# Supply.net
KiCad netlist of a schematic drawn in Altium Designer
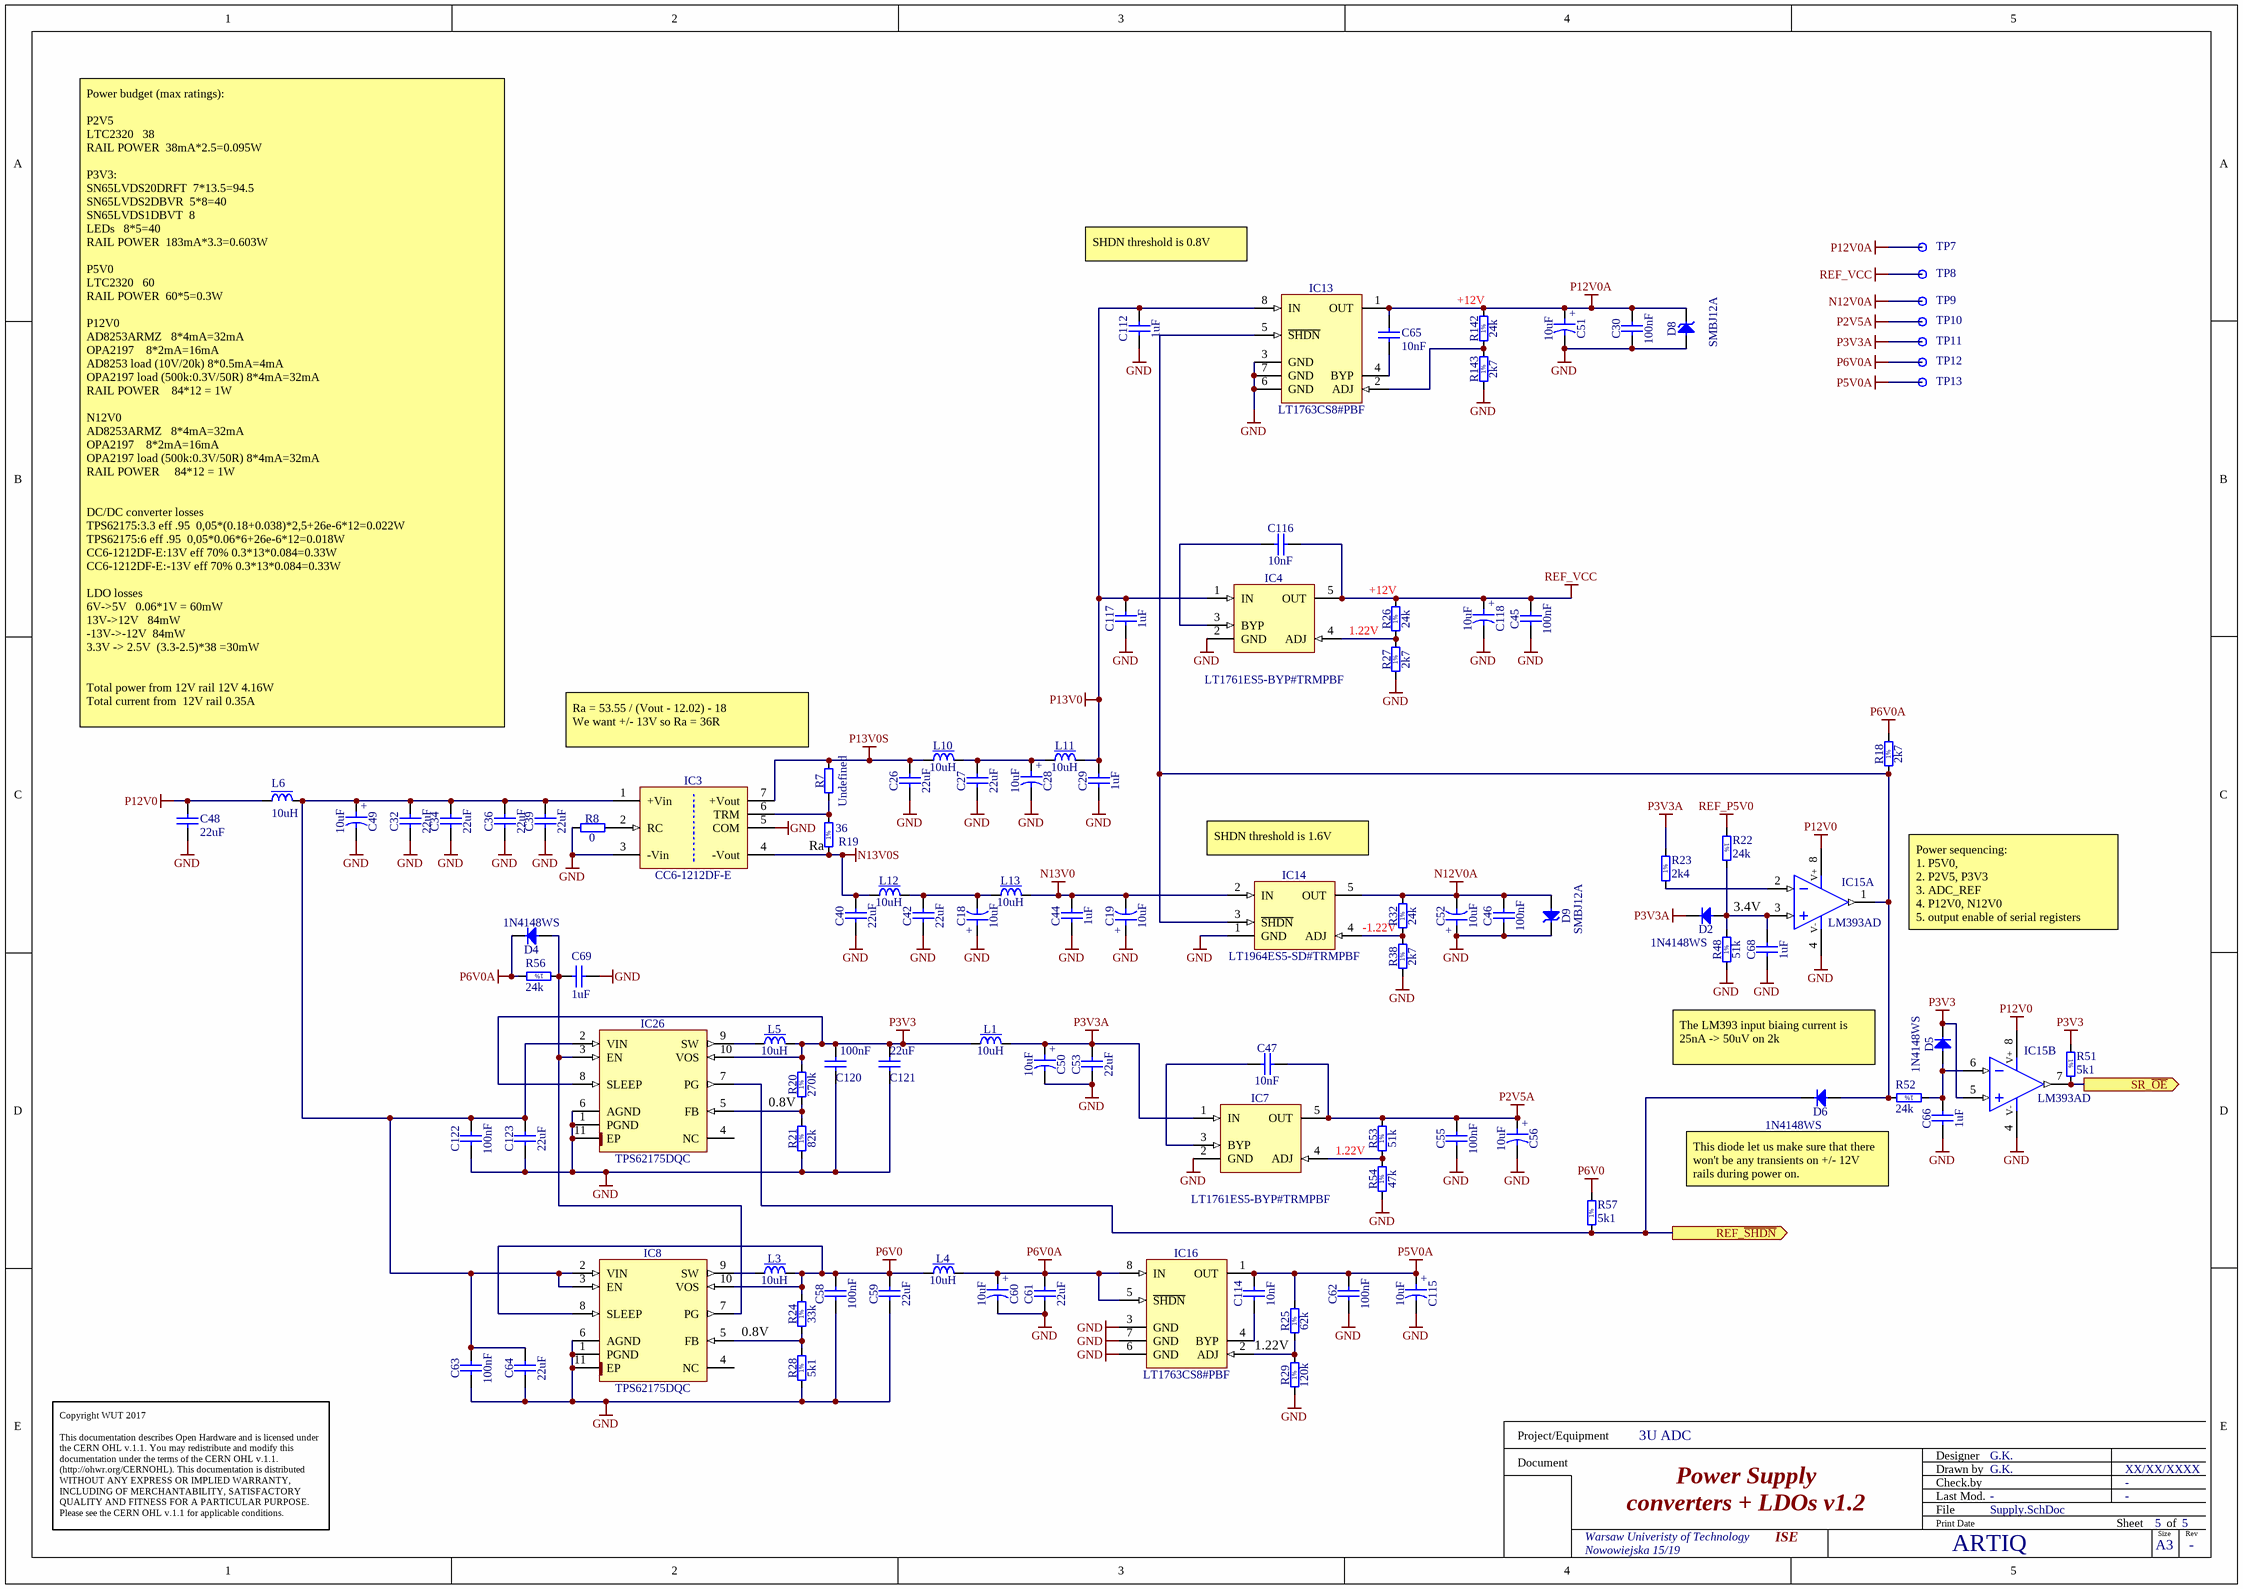
[diagram p0: Supply.SchDoc]

(export (version "E")
  (design (tool "Eeschema 10.0.6"))
  (components
    (comp (ref "C18")
      (value "10uF")
      (footprint "CAPMP3216X180N")
      (description "Polarised capacitor")
      (fields (field (name "PART NUMBER") "CTE3216-18_10UF_16V_20%_AVX_TCJ") (field (name "VOLTAGE") "16V"))
      (libsource (lib "Capacitors") (part "Capacitor - polarized"))
    )
    (comp (ref "C19")
      (value "10uF")
      (footprint "CAPMP3216X180N")
      (description "Polarised capacitor")
      (fields (field (name "PART NUMBER") "CTE3216-18_10UF_16V_20%_AVX_TCJ") (field (name "VOLTAGE") "16V"))
      (libsource (lib "Capacitors") (part "Capacitor - polarized"))
    )
    (comp (ref "C26")
      (value "22uF")
      (footprint "CAPC2012X135N")
      (description "Non-polarised capacitor")
      (fields (field (name "PART NUMBER") "CC0805_22UF_16V_10%_X5R") (field (name "VOLTAGE") "16V"))
      (libsource (lib "Capacitors") (part "Capacitor - non polarized"))
    )
    (comp (ref "C27")
      (value "22uF")
      (footprint "CAPC2012X135N")
      (description "Non-polarised capacitor")
      (fields (field (name "PART NUMBER") "CC0805_22UF_16V_10%_X5R") (field (name "VOLTAGE") "16V"))
      (libsource (lib "Capacitors") (part "Capacitor - non polarized"))
    )
    (comp (ref "C28")
      (value "10uF")
      (footprint "CAPMP3216X180N")
      (description "Polarised capacitor")
      (fields (field (name "PART NUMBER") "CTE3216-18_10UF_16V_20%_AVX_TCJ") (field (name "VOLTAGE") "16V"))
      (libsource (lib "Capacitors") (part "Capacitor - polarized"))
    )
    (comp (ref "C29")
      (value "1uF")
      (footprint "CAPC1608X87N")
      (description "Non-polarised capacitor")
      (fields (field (name "PART NUMBER") "CC0603_1UF_25V_10%_X7R") (field (name "VOLTAGE") "25V"))
      (libsource (lib "Capacitors") (part "Capacitor - non polarized"))
    )
    (comp (ref "C30")
      (value "100nF")
      (footprint "CAPC1005X55N")
      (description "Non-polarised capacitor")
      (fields (field (name "PART NUMBER") "CC0402_100NF_16V_10%_X5R") (field (name "VOLTAGE") "16V"))
      (libsource (lib "Capacitors") (part "Capacitor - non polarized"))
    )
    (comp (ref "C32")
      (value "22uF")
      (footprint "CAPC2012X135N")
      (description "Non-polarised capacitor")
      (fields (field (name "PART NUMBER") "CC0805_22UF_16V_10%_X5R") (field (name "VOLTAGE") "16V"))
      (libsource (lib "Capacitors") (part "Capacitor - non polarized"))
    )
    (comp (ref "C34")
      (value "22uF")
      (footprint "CAPC2012X135N")
      (description "Non-polarised capacitor")
      (fields (field (name "PART NUMBER") "CC0805_22UF_16V_10%_X5R") (field (name "VOLTAGE") "16V"))
      (libsource (lib "Capacitors") (part "Capacitor - non polarized"))
    )
    (comp (ref "C36")
      (value "22uF")
      (footprint "CAPC2012X135N")
      (description "Non-polarised capacitor")
      (fields (field (name "PART NUMBER") "CC0805_22UF_16V_10%_X5R") (field (name "VOLTAGE") "16V"))
      (libsource (lib "Capacitors") (part "Capacitor - non polarized"))
    )
    (comp (ref "C39")
      (value "22uF")
      (footprint "CAPC2012X135N")
      (description "Non-polarised capacitor")
      (fields (field (name "PART NUMBER") "CC0805_22UF_16V_10%_X5R") (field (name "VOLTAGE") "16V"))
      (libsource (lib "Capacitors") (part "Capacitor - non polarized"))
    )
    (comp (ref "C40")
      (value "22uF")
      (footprint "CAPC2012X135N")
      (description "Non-polarised capacitor")
      (fields (field (name "PART NUMBER") "CC0805_22UF_16V_10%_X5R") (field (name "VOLTAGE") "16V"))
      (libsource (lib "Capacitors") (part "Capacitor - non polarized"))
    )
    (comp (ref "C42")
      (value "22uF")
      (footprint "CAPC2012X135N")
      (description "Non-polarised capacitor")
      (fields (field (name "PART NUMBER") "CC0805_22UF_16V_10%_X5R") (field (name "VOLTAGE") "16V"))
      (libsource (lib "Capacitors") (part "Capacitor - non polarized"))
    )
    (comp (ref "C44")
      (value "1uF")
      (footprint "CAPC1608X87N")
      (description "Non-polarised capacitor")
      (fields (field (name "PART NUMBER") "CC0603_1UF_25V_10%_X7R") (field (name "VOLTAGE") "25V"))
      (libsource (lib "Capacitors") (part "Capacitor - non polarized"))
    )
    (comp (ref "C45")
      (value "100nF")
      (footprint "CAPC1005X55N")
      (description "Non-polarised capacitor")
      (fields (field (name "PART NUMBER") "CC0402_100NF_16V_10%_X5R") (field (name "VOLTAGE") "16V"))
      (libsource (lib "Capacitors") (part "Capacitor - non polarized"))
    )
    (comp (ref "C46")
      (value "100nF")
      (footprint "CAPC1005X55N")
      (description "Non-polarised capacitor")
      (fields (field (name "PART NUMBER") "CC0402_100NF_16V_10%_X5R") (field (name "VOLTAGE") "16V"))
      (libsource (lib "Capacitors") (part "Capacitor - non polarized"))
    )
    (comp (ref "C47")
      (value "10nF")
      (footprint "CAPC1608X87N")
      (description "Non-polarised capacitor")
      (fields (field (name "PART NUMBER") "CC0603_10NF_50V_10%_X7R") (field (name "VOLTAGE") "50V"))
      (libsource (lib "Capacitors") (part "Capacitor - non polarized"))
    )
    (comp (ref "C48")
      (value "22uF")
      (footprint "CAPC2012X135N")
      (description "Non-polarised capacitor")
      (fields (field (name "PART NUMBER") "CC0805_22UF_16V_10%_X5R") (field (name "VOLTAGE") "16V"))
      (libsource (lib "Capacitors") (part "Capacitor - non polarized"))
    )
    (comp (ref "C49")
      (value "10uF")
      (footprint "CAPMP3216X180N")
      (description "Polarised capacitor")
      (fields (field (name "PART NUMBER") "CTE3216-18_10UF_16V_20%_AVX_TCJ") (field (name "VOLTAGE") "16V"))
      (libsource (lib "Capacitors") (part "Capacitor - polarized"))
    )
    (comp (ref "C50")
      (value "10uF")
      (footprint "CAPMP3216X180N")
      (description "Polarised capacitor")
      (fields (field (name "PART NUMBER") "CTE3216-18_10UF_16V_20%_AVX_TCJ") (field (name "VOLTAGE") "16V"))
      (libsource (lib "Capacitors") (part "Capacitor - polarized"))
    )
    (comp (ref "C51")
      (value "10uF")
      (footprint "CAPMP3216X180N")
      (description "Polarised capacitor")
      (fields (field (name "PART NUMBER") "CTE3216-18_10UF_16V_20%_AVX_TCJ") (field (name "VOLTAGE") "16V"))
      (libsource (lib "Capacitors") (part "Capacitor - polarized"))
    )
    (comp (ref "C52")
      (value "10uF")
      (footprint "CAPMP3216X180N")
      (description "Polarised capacitor")
      (fields (field (name "PART NUMBER") "CTE3216-18_10UF_16V_20%_AVX_TCJ") (field (name "VOLTAGE") "16V"))
      (libsource (lib "Capacitors") (part "Capacitor - polarized"))
    )
    (comp (ref "C53")
      (value "22uF")
      (footprint "CAPC2012X135N")
      (description "Non-polarised capacitor")
      (fields (field (name "PART NUMBER") "CC0805_22UF_16V_10%_X5R") (field (name "VOLTAGE") "16V"))
      (libsource (lib "Capacitors") (part "Capacitor - non polarized"))
    )
    (comp (ref "C55")
      (value "100nF")
      (footprint "CAPC1005X55N")
      (description "Non-polarised capacitor")
      (fields (field (name "PART NUMBER") "CC0402_100NF_16V_10%_X5R") (field (name "VOLTAGE") "16V"))
      (libsource (lib "Capacitors") (part "Capacitor - non polarized"))
    )
    (comp (ref "C56")
      (value "10uF")
      (footprint "CAPMP3216X180N")
      (description "Polarised capacitor")
      (fields (field (name "PART NUMBER") "CTE3216-18_10UF_16V_20%_AVX_TCJ") (field (name "VOLTAGE") "16V"))
      (libsource (lib "Capacitors") (part "Capacitor - polarized"))
    )
    (comp (ref "C58")
      (value "100nF")
      (footprint "CAPC1005X55N")
      (description "Non-polarised capacitor")
      (fields (field (name "PART NUMBER") "CC0402_100NF_16V_10%_X5R") (field (name "VOLTAGE") "16V"))
      (libsource (lib "Capacitors") (part "Capacitor - non polarized"))
    )
    (comp (ref "C59")
      (value "22uF")
      (footprint "CAPC2012X135N")
      (description "Non-polarised capacitor")
      (fields (field (name "PART NUMBER") "CC0805_22UF_16V_10%_X5R") (field (name "VOLTAGE") "16V"))
      (libsource (lib "Capacitors") (part "Capacitor - non polarized"))
    )
    (comp (ref "C60")
      (value "10uF")
      (footprint "CAPMP3216X180N")
      (description "Polarised capacitor")
      (fields (field (name "PART NUMBER") "CTE3216-18_10UF_16V_20%_AVX_TCJ") (field (name "VOLTAGE") "16V"))
      (libsource (lib "Capacitors") (part "Capacitor - polarized"))
    )
    (comp (ref "C61")
      (value "22uF")
      (footprint "CAPC2012X135N")
      (description "Non-polarised capacitor")
      (fields (field (name "PART NUMBER") "CC0805_22UF_16V_10%_X5R") (field (name "VOLTAGE") "16V"))
      (libsource (lib "Capacitors") (part "Capacitor - non polarized"))
    )
    (comp (ref "C62")
      (value "100nF")
      (footprint "CAPC1005X55N")
      (description "Non-polarised capacitor")
      (fields (field (name "PART NUMBER") "CC0402_100NF_16V_10%_X5R") (field (name "VOLTAGE") "16V"))
      (libsource (lib "Capacitors") (part "Capacitor - non polarized"))
    )
    (comp (ref "C63")
      (value "100nF")
      (footprint "CAPC1005X55N")
      (description "Non-polarised capacitor")
      (fields (field (name "PART NUMBER") "CC0402_100NF_16V_10%_X5R") (field (name "VOLTAGE") "16V"))
      (libsource (lib "Capacitors") (part "Capacitor - non polarized"))
    )
    (comp (ref "C64")
      (value "22uF")
      (footprint "CAPC2012X135N")
      (description "Non-polarised capacitor")
      (fields (field (name "PART NUMBER") "CC0805_22UF_16V_10%_X5R") (field (name "VOLTAGE") "16V"))
      (libsource (lib "Capacitors") (part "Capacitor - non polarized"))
    )
    (comp (ref "C65")
      (value "10nF")
      (footprint "CAPC1608X87N")
      (description "Non-polarised capacitor")
      (fields (field (name "PART NUMBER") "CC0603_10NF_50V_10%_X7R") (field (name "VOLTAGE") "50V"))
      (libsource (lib "Capacitors") (part "Capacitor - non polarized"))
    )
    (comp (ref "C66")
      (value "1uF")
      (footprint "CAPC1608X87N")
      (description "Non-polarised capacitor")
      (fields (field (name "PART NUMBER") "CC0603_1UF_25V_10%_X7R") (field (name "VOLTAGE") "25V"))
      (libsource (lib "Capacitors") (part "Capacitor - non polarized"))
    )
    (comp (ref "C68")
      (value "1uF")
      (footprint "CAPC1608X87N")
      (description "Non-polarised capacitor")
      (fields (field (name "PART NUMBER") "CC0603_1UF_25V_10%_X7R") (field (name "VOLTAGE") "25V"))
      (libsource (lib "Capacitors") (part "Capacitor - non polarized"))
    )
    (comp (ref "C69")
      (value "1uF")
      (footprint "CAPC1608X87N")
      (description "Non-polarised capacitor")
      (fields (field (name "PART NUMBER") "CC0603_1UF_25V_10%_X7R") (field (name "VOLTAGE") "25V"))
      (libsource (lib "Capacitors") (part "Capacitor - non polarized"))
    )
    (comp (ref "C112")
      (value "1uF")
      (footprint "CAPC1608X87N")
      (description "Non-polarised capacitor")
      (fields (field (name "PART NUMBER") "CC0603_1UF_25V_10%_X7R") (field (name "VOLTAGE") "25V"))
      (libsource (lib "Capacitors") (part "Capacitor - non polarized"))
    )
    (comp (ref "C114")
      (value "10nF")
      (footprint "CAPC1608X87N")
      (description "Non-polarised capacitor")
      (fields (field (name "PART NUMBER") "CC0603_10NF_50V_10%_X7R") (field (name "VOLTAGE") "50V"))
      (libsource (lib "Capacitors") (part "Capacitor - non polarized"))
    )
    (comp (ref "C115")
      (value "10uF")
      (footprint "CAPMP3216X180N")
      (description "Polarised capacitor")
      (fields (field (name "PART NUMBER") "CTE3216-18_10UF_16V_20%_AVX_TCJ") (field (name "VOLTAGE") "16V"))
      (libsource (lib "Capacitors") (part "Capacitor - polarized"))
    )
    (comp (ref "C116")
      (value "10nF")
      (footprint "CAPC1608X87N")
      (description "Non-polarised capacitor")
      (fields (field (name "PART NUMBER") "CC0603_10NF_50V_10%_X7R") (field (name "VOLTAGE") "50V"))
      (libsource (lib "Capacitors") (part "Capacitor - non polarized"))
    )
    (comp (ref "C117")
      (value "1uF")
      (footprint "CAPC1608X87N")
      (description "Non-polarised capacitor")
      (fields (field (name "PART NUMBER") "CC0603_1UF_25V_10%_X7R") (field (name "VOLTAGE") "25V"))
      (libsource (lib "Capacitors") (part "Capacitor - non polarized"))
    )
    (comp (ref "C118")
      (value "10uF")
      (footprint "CAPMP3216X180N")
      (description "Polarised capacitor")
      (fields (field (name "PART NUMBER") "CTE3216-18_10UF_16V_20%_AVX_TCJ") (field (name "VOLTAGE") "16V"))
      (libsource (lib "Capacitors") (part "Capacitor - polarized"))
    )
    (comp (ref "C120")
      (value "100nF")
      (footprint "CAPC1005X55N")
      (description "Non-polarised capacitor")
      (fields (field (name "PART NUMBER") "CC0402_100NF_16V_10%_X5R") (field (name "VOLTAGE") "16V"))
      (libsource (lib "Capacitors") (part "Capacitor - non polarized"))
    )
    (comp (ref "C121")
      (value "22uF")
      (footprint "CAPC2012X135N")
      (description "Non-polarised capacitor")
      (fields (field (name "PART NUMBER") "CC0805_22UF_16V_10%_X5R") (field (name "VOLTAGE") "16V"))
      (libsource (lib "Capacitors") (part "Capacitor - non polarized"))
    )
    (comp (ref "C122")
      (value "100nF")
      (footprint "CAPC1005X55N")
      (description "Non-polarised capacitor")
      (fields (field (name "PART NUMBER") "CC0402_100NF_16V_10%_X5R") (field (name "VOLTAGE") "16V"))
      (libsource (lib "Capacitors") (part "Capacitor - non polarized"))
    )
    (comp (ref "C123")
      (value "22uF")
      (footprint "CAPC2012X135N")
      (description "Non-polarised capacitor")
      (fields (field (name "PART NUMBER") "CC0805_22UF_16V_10%_X5R") (field (name "VOLTAGE") "16V"))
      (libsource (lib "Capacitors") (part "Capacitor - non polarized"))
    )
    (comp (ref "D2")
      (value "1N4148WS")
      (footprint "SODFL2512X100N")
      (description "Diode")
      (fields (field (name "VOLTAGE") "75V") (field (name "POWER") "150mA"))
      (libsource (lib "ICs And Semiconductors") (part "Diode"))
    )
    (comp (ref "D4")
      (value "1N4148WS")
      (footprint "SODFL2512X100N")
      (description "Diode")
      (fields (field (name "VOLTAGE") "75V") (field (name "POWER") "150mA"))
      (libsource (lib "ICs And Semiconductors") (part "Diode"))
    )
    (comp (ref "D5")
      (value "1N4148WS")
      (footprint "SODFL2512X100N")
      (description "Diode")
      (fields (field (name "VOLTAGE") "75V") (field (name "POWER") "150mA"))
      (libsource (lib "ICs And Semiconductors") (part "Diode"))
    )
    (comp (ref "D6")
      (value "1N4148WS")
      (footprint "SODFL2512X100N")
      (description "Diode")
      (fields (field (name "VOLTAGE") "75V") (field (name "POWER") "150mA"))
      (libsource (lib "ICs And Semiconductors") (part "Diode"))
    )
    (comp (ref "D8")
      (value "SMBJ12A")
      (footprint "DIOM5336X265N")
      (description "Zener Diode")
      (fields (field (name "VOLTAGE") "12V") (field (name "POWER") "600W"))
      (libsource (lib "ICs And Semiconductors") (part "Diode Zener"))
    )
    (comp (ref "D9")
      (value "SMBJ12A")
      (footprint "DIOM5336X265N")
      (description "Zener Diode")
      (fields (field (name "VOLTAGE") "12V") (field (name "POWER") "600W"))
      (libsource (lib "ICs And Semiconductors") (part "Diode Zener"))
    )
    (comp (ref "IC3")
      (value "CC6-1212DF-E")
      (footprint "CC6-1212DF-E")
      (description "CONV DC/DC 6W DUAL 12V +-12V PCB")
      (fields (field (name "MANUFACTURER") "TDK-Lambda Americas Inc."))
      (libsource (lib "LIBRARY_SCH") (part "DC/DC_CC6-1212DF-E"))
    )
    (comp (ref "IC4")
      (value "LT1761ES5-BYP#TRMPBF")
      (footprint "SOT95P280X100-5N")
      (description "100mA, Low Noise, LDO Micropower Adjustable Regulator in SOT-23")
      (fields (field (name "MANUFACTURER") "LINEAR TECHNOLOGY"))
      (libsource (lib "ICs And Semiconductors") (part "LT1761-BYP"))
    )
    (comp (ref "IC7")
      (value "LT1761ES5-BYP#TRMPBF")
      (footprint "SOT95P280X100-5N")
      (description "100mA, Low Noise, LDO Micropower Adjustable Regulator in SOT-23")
      (fields (field (name "MANUFACTURER") "LINEAR TECHNOLOGY"))
      (libsource (lib "ICs And Semiconductors") (part "LT1761-BYP"))
    )
    (comp (ref "IC8")
      (value "TPS62175DQC")
      (footprint "SON50P200X300X80-11N-R94X250")
      (description "4.75-28VDC to 1-6VDC, 500mA Step-Down Converter With Sleep Mode")
      (fields (field (name "MANUFACTURER") "TEXAS INSTRUMENTS"))
      (libsource (lib "ICs And Semiconductors") (part "TPS62175"))
    )
    (comp (ref "IC13")
      (value "LT1763CS8#PBF")
      (footprint "SOIC127P600X175-8N")
      (description "1.22V to 20V 500mA, Low Noise, LDO Adjustable Micropower Regulator")
      (fields (field (name "MANUFACTURER") "LINEAR TECHNOLOGY"))
      (libsource (lib "ICs And Semiconductors") (part "LT1763xS8"))
    )
    (comp (ref "IC14")
      (value "LT1964ES5-SD#TRMPBF")
      (footprint "SOT95P280X100-5N")
      (description "200mA, Low Noise, Low Dropout Negative Micropower Regulator")
      (fields (field (name "MANUFACTURER") "LINEAR TECHNOLOGY"))
      (libsource (lib "ICs And Semiconductors") (part "LT1964-SD"))
    )
    (comp (ref "IC15")
      (value "LM393AD")
      (footprint "SOIC127P600X175-8N")
      (description "Dual Operational Amplifier")
      (fields (field (name "MANUFACTURER") "TEXAS INSTRUMENTS"))
      (libsource (lib "ICs And Semiconductors") (part "Operational Amplifier x2 Type1"))
    )
    (comp (ref "IC16")
      (value "LT1763CS8#PBF")
      (footprint "SOIC127P600X175-8N")
      (description "1.22V to 20V 500mA, Low Noise, LDO Adjustable Micropower Regulator")
      (fields (field (name "MANUFACTURER") "LINEAR TECHNOLOGY"))
      (libsource (lib "ICs And Semiconductors") (part "LT1763xS8"))
    )
    (comp (ref "IC26")
      (value "TPS62175DQC")
      (footprint "SON50P200X300X80-11N-R94X250")
      (description "4.75-28VDC to 1-6VDC, 500mA Step-Down Converter With Sleep Mode")
      (fields (field (name "MANUFACTURER") "TEXAS INSTRUMENTS"))
      (libsource (lib "ICs And Semiconductors") (part "TPS62175"))
    )
    (comp (ref "L1")
      (value "10uH")
      (footprint "IND_MURATA-PS_8400")
      (description "Inductor With Core")
      (fields (field (name "PART NUMBER") "IND_10UH_10%_MURATA-PS_8400") (field (name "POWER") "950mA"))
      (libsource (lib "Inductors & Transformers") (part "Inductor With Magnetic core"))
    )
    (comp (ref "L3")
      (value "10uH")
      (footprint "IND_MURATA-PS_8400")
      (description "Inductor With Core")
      (fields (field (name "PART NUMBER") "IND_10UH_10%_MURATA-PS_8400") (field (name "POWER") "950mA"))
      (libsource (lib "Inductors & Transformers") (part "Inductor With Magnetic core"))
    )
    (comp (ref "L4")
      (value "10uH")
      (footprint "IND_MURATA-PS_8400")
      (description "Inductor With Core")
      (fields (field (name "PART NUMBER") "IND_10UH_10%_MURATA-PS_8400") (field (name "POWER") "950mA"))
      (libsource (lib "Inductors & Transformers") (part "Inductor With Magnetic core"))
    )
    (comp (ref "L5")
      (value "10uH")
      (footprint "IND_MURATA-PS_8400")
      (description "Inductor With Core")
      (fields (field (name "PART NUMBER") "IND_10UH_10%_MURATA-PS_8400") (field (name "POWER") "950mA"))
      (libsource (lib "Inductors & Transformers") (part "Inductor With Magnetic core"))
    )
    (comp (ref "L6")
      (value "10uH")
      (footprint "IND_MURATA-PS_8400")
      (description "Inductor With Core")
      (fields (field (name "PART NUMBER") "IND_10UH_10%_MURATA-PS_8400") (field (name "POWER") "950mA"))
      (libsource (lib "Inductors & Transformers") (part "Inductor With Magnetic core"))
    )
    (comp (ref "L10")
      (value "10uH")
      (footprint "IND_MURATA-PS_8400")
      (description "Inductor With Core")
      (fields (field (name "PART NUMBER") "IND_10UH_10%_MURATA-PS_8400") (field (name "POWER") "950mA"))
      (libsource (lib "Inductors & Transformers") (part "Inductor With Magnetic core"))
    )
    (comp (ref "L11")
      (value "10uH")
      (footprint "IND_MURATA-PS_8400")
      (description "Inductor With Core")
      (fields (field (name "PART NUMBER") "IND_10UH_10%_MURATA-PS_8400") (field (name "POWER") "950mA"))
      (libsource (lib "Inductors & Transformers") (part "Inductor With Magnetic core"))
    )
    (comp (ref "L12")
      (value "10uH")
      (footprint "IND_MURATA-PS_8400")
      (description "Inductor With Core")
      (fields (field (name "PART NUMBER") "IND_10UH_10%_MURATA-PS_8400") (field (name "POWER") "950mA"))
      (libsource (lib "Inductors & Transformers") (part "Inductor With Magnetic core"))
    )
    (comp (ref "L13")
      (value "10uH")
      (footprint "IND_MURATA-PS_8400")
      (description "Inductor With Core")
      (fields (field (name "PART NUMBER") "IND_10UH_10%_MURATA-PS_8400") (field (name "POWER") "950mA"))
      (libsource (lib "Inductors & Transformers") (part "Inductor With Magnetic core"))
    )
    (comp (ref "R7")
      (value "Undefined")
      (footprint "RESC1608X55N")
      (description "Resistor")
      (fields (field (name "PART NUMBER") "R0603_NO-VALUE"))
      (libsource (lib "Resistors") (part "Resistor"))
    )
    (comp (ref "R8")
      (value "0")
      (footprint "RESC1005X40N")
      (description "Resistor")
      (fields (field (name "PART NUMBER") "R0402_0R_JUMPER") (field (name "MANUFACTURER") "GENERIC"))
      (libsource (lib "Resistors") (part "Resistor"))
    )
    (comp (ref "R18")
      (value "2k7")
      (footprint "RESC1608X55N")
      (description "Resistor - 1%")
      (fields (field (name "PART NUMBER") "R0603_2K7_1%_0.1W_100PPM") (field (name "POWER") "0.1W"))
      (libsource (lib "Resistors") (part "Resistor - 1%"))
    )
    (comp (ref "R19")
      (value "36")
      (footprint "RESC1005X40N")
      (description "Resistor - 1%")
      (fields (field (name "PART NUMBER") "R0402_36R_1%_0.0625W_100PPM") (field (name "POWER") "0.0625W"))
      (libsource (lib "Resistors") (part "Resistor - 1%"))
    )
    (comp (ref "R20")
      (value "270k")
      (footprint "RESC1608X55N")
      (description "Resistor - 1%")
      (fields (field (name "PART NUMBER") "R0603_270K_1%_0.1W_100PPM") (field (name "POWER") "0.1W"))
      (libsource (lib "Resistors") (part "Resistor - 1%"))
    )
    (comp (ref "R21")
      (value "82k")
      (footprint "RESC1608X55N")
      (description "Resistor - 1%")
      (fields (field (name "PART NUMBER") "R0603_82K_1%_0.1W_100PPM") (field (name "POWER") "0.1W"))
      (libsource (lib "Resistors") (part "Resistor - 1%"))
    )
    (comp (ref "R22")
      (value "24k")
      (footprint "RESC1608X55N")
      (description "Resistor - 1%")
      (fields (field (name "PART NUMBER") "R0603_24K_1%_0.1W_100PPM") (field (name "POWER") "0.1W"))
      (libsource (lib "Resistors") (part "Resistor - 1%"))
    )
    (comp (ref "R23")
      (value "2k4")
      (footprint "RESC1005X40N")
      (description "Resistor - 1%")
      (fields (field (name "PART NUMBER") "R0402_2K4_1%_0.0625W_100PPM") (field (name "POWER") "0.0625W"))
      (libsource (lib "Resistors") (part "Resistor - 1%"))
    )
    (comp (ref "R24")
      (value "33k")
      (footprint "RESC1005X40N")
      (description "Resistor - 1%")
      (fields (field (name "PART NUMBER") "R0402_33K_1%_0.0625W_100PPM") (field (name "POWER") "0.0625W"))
      (libsource (lib "Resistors") (part "Resistor - 1%"))
    )
    (comp (ref "R25")
      (value "62k")
      (footprint "RESC1005X40N")
      (description "Resistor - 1%")
      (fields (field (name "PART NUMBER") "R0402_62K_1%_0.0625W_100PPM") (field (name "POWER") "0.0625W"))
      (libsource (lib "Resistors") (part "Resistor - 1%"))
    )
    (comp (ref "R26")
      (value "24k")
      (footprint "RESC1608X55N")
      (description "Resistor - 1%")
      (fields (field (name "PART NUMBER") "R0603_24K_1%_0.1W_100PPM") (field (name "POWER") "0.1W"))
      (libsource (lib "Resistors") (part "Resistor - 1%"))
    )
    (comp (ref "R27")
      (value "2k7")
      (footprint "RESC1608X55N")
      (description "Resistor - 1%")
      (fields (field (name "PART NUMBER") "R0603_2K7_1%_0.1W_100PPM") (field (name "POWER") "0.1W"))
      (libsource (lib "Resistors") (part "Resistor - 1%"))
    )
    (comp (ref "R28")
      (value "5k1")
      (footprint "RESC1005X40N")
      (description "Resistor - 1%")
      (fields (field (name "PART NUMBER") "R0402_5K1_1%_0.0625W_100PPM") (field (name "POWER") "0.0625W"))
      (libsource (lib "Resistors") (part "Resistor - 1%"))
    )
    (comp (ref "R29")
      (value "120k")
      (footprint "RESC1005X40N")
      (description "Resistor - 1%")
      (fields (field (name "PART NUMBER") "R0402_120K_1%_0.0625W_100PPM") (field (name "POWER") "0.0625W"))
      (libsource (lib "Resistors") (part "Resistor - 1%"))
    )
    (comp (ref "R32")
      (value "24k")
      (footprint "RESC1608X55N")
      (description "Resistor - 1%")
      (fields (field (name "PART NUMBER") "R0603_24K_1%_0.1W_100PPM") (field (name "POWER") "0.1W"))
      (libsource (lib "Resistors") (part "Resistor - 1%"))
    )
    (comp (ref "R38")
      (value "2k7")
      (footprint "RESC1608X55N")
      (description "Resistor - 1%")
      (fields (field (name "PART NUMBER") "R0603_2K7_1%_0.1W_100PPM") (field (name "POWER") "0.1W"))
      (libsource (lib "Resistors") (part "Resistor - 1%"))
    )
    (comp (ref "R48")
      (value "51k")
      (footprint "RESC1005X40N")
      (description "Resistor - 1%")
      (fields (field (name "PART NUMBER") "R0402_51K_1%_0.0625W_100PPM") (field (name "POWER") "0.0625W"))
      (libsource (lib "Resistors") (part "Resistor - 1%"))
    )
    (comp (ref "R51")
      (value "5k1")
      (footprint "RESC1005X40N")
      (description "Resistor - 1%")
      (fields (field (name "PART NUMBER") "R0402_5K1_1%_0.0625W_100PPM") (field (name "POWER") "0.0625W"))
      (libsource (lib "Resistors") (part "Resistor - 1%"))
    )
    (comp (ref "R52")
      (value "24k")
      (footprint "RESC1608X55N")
      (description "Resistor - 1%")
      (fields (field (name "PART NUMBER") "R0603_24K_1%_0.1W_100PPM") (field (name "POWER") "0.1W"))
      (libsource (lib "Resistors") (part "Resistor - 1%"))
    )
    (comp (ref "R53")
      (value "51k")
      (footprint "RESC1005X40N")
      (description "Resistor - 1%")
      (fields (field (name "PART NUMBER") "R0402_51K_1%_0.0625W_100PPM") (field (name "POWER") "0.0625W"))
      (libsource (lib "Resistors") (part "Resistor - 1%"))
    )
    (comp (ref "R54")
      (value "47k")
      (footprint "RESC1005X40N")
      (description "Resistor - 1%")
      (fields (field (name "PART NUMBER") "R0402_47K_1%_0.0625W_100PPM") (field (name "POWER") "0.0625W"))
      (libsource (lib "Resistors") (part "Resistor - 1%"))
    )
    (comp (ref "R56")
      (value "24k")
      (footprint "RESC1608X55N")
      (description "Resistor - 1%")
      (fields (field (name "PART NUMBER") "R0603_24K_1%_0.1W_100PPM") (field (name "POWER") "0.1W"))
      (libsource (lib "Resistors") (part "Resistor - 1%"))
    )
    (comp (ref "R57")
      (value "5k1")
      (footprint "RESC1005X40N")
      (description "Resistor - 1%")
      (fields (field (name "PART NUMBER") "R0402_5K1_1%_0.0625W_100PPM") (field (name "POWER") "0.0625W"))
      (libsource (lib "Resistors") (part "Resistor - 1%"))
    )
    (comp (ref "R142")
      (value "24k")
      (footprint "RESC1608X55N")
      (description "Resistor - 1%")
      (fields (field (name "PART NUMBER") "R0603_24K_1%_0.1W_100PPM") (field (name "POWER") "0.1W"))
      (libsource (lib "Resistors") (part "Resistor - 1%"))
    )
    (comp (ref "R143")
      (value "2k7")
      (footprint "RESC1608X55N")
      (description "Resistor - 1%")
      (fields (field (name "PART NUMBER") "R0603_2K7_1%_0.1W_100PPM") (field (name "POWER") "0.1W"))
      (libsource (lib "Resistors") (part "Resistor - 1%"))
    )
    (comp (ref "TP7")
      (value "Test Point")
      (footprint "TPS127")
      (fields (field (name "PART NUMBER") "SMD_PAD_1.27X1.27MM"))
      (libsource (lib "Eletro-mechanical") (part "Test Point"))
    )
    (comp (ref "TP8")
      (value "Test Point")
      (footprint "TPS127")
      (fields (field (name "PART NUMBER") "SMD_PAD_1.27X1.27MM"))
      (libsource (lib "Eletro-mechanical") (part "Test Point"))
    )
    (comp (ref "TP9")
      (value "Test Point")
      (footprint "TPS127")
      (fields (field (name "PART NUMBER") "SMD_PAD_1.27X1.27MM"))
      (libsource (lib "Eletro-mechanical") (part "Test Point"))
    )
    (comp (ref "TP10")
      (value "Test Point")
      (footprint "TPS127")
      (fields (field (name "PART NUMBER") "SMD_PAD_1.27X1.27MM"))
      (libsource (lib "Eletro-mechanical") (part "Test Point"))
    )
    (comp (ref "TP11")
      (value "Test Point")
      (footprint "TPS127")
      (fields (field (name "PART NUMBER") "SMD_PAD_1.27X1.27MM"))
      (libsource (lib "Eletro-mechanical") (part "Test Point"))
    )
    (comp (ref "TP12")
      (value "Test Point")
      (footprint "TPS127")
      (fields (field (name "PART NUMBER") "SMD_PAD_1.27X1.27MM"))
      (libsource (lib "Eletro-mechanical") (part "Test Point"))
    )
    (comp (ref "TP13")
      (value "Test Point")
      (footprint "TPS127")
      (fields (field (name "PART NUMBER") "SMD_PAD_1.27X1.27MM"))
      (libsource (lib "Eletro-mechanical") (part "Test Point"))
    )
  )
  (nets
    (net (code "1") (name "/REF_~{SHDN}") (class "Default")
      (node (ref "D6") (pin "1") (pinfunction "C_1") (pintype "passive"))
      (node (ref "IC26") (pin "7") (pinfunction "PG_7") (pintype "output"))
      (node (ref "R57") (pin "1") (pinfunction "1_1") (pintype "passive"))
    )
    (net (code "2") (name "/SR_~{OE}") (class "Default")
      (node (ref "IC15") (pin "7") (pinfunction "OUT_7") (pintype "output"))
      (node (ref "R51") (pin "2") (pinfunction "2_2") (pintype "passive"))
    )
    (net (code "3") (name "GND") (class "Default")
      (node (ref "C112") (pin "1") (pinfunction "1_1") (pintype "passive"))
      (node (ref "C115") (pin "2") (pinfunction "2_2") (pintype "passive"))
      (node (ref "C117") (pin "1") (pinfunction "1_1") (pintype "passive"))
      (node (ref "C118") (pin "2") (pinfunction "2_2") (pintype "passive"))
      (node (ref "C120") (pin "1") (pinfunction "1_1") (pintype "passive"))
      (node (ref "C121") (pin "1") (pinfunction "1_1") (pintype "passive"))
      (node (ref "C122") (pin "1") (pinfunction "1_1") (pintype "passive"))
      (node (ref "C123") (pin "1") (pinfunction "1_1") (pintype "passive"))
      (node (ref "C18") (pin "1") (pinfunction "1_1") (pintype "passive"))
      (node (ref "C19") (pin "1") (pinfunction "1_1") (pintype "passive"))
      (node (ref "C26") (pin "1") (pinfunction "1_1") (pintype "passive"))
      (node (ref "C27") (pin "1") (pinfunction "1_1") (pintype "passive"))
      (node (ref "C28") (pin "2") (pinfunction "2_2") (pintype "passive"))
      (node (ref "C29") (pin "1") (pinfunction "1_1") (pintype "passive"))
      (node (ref "C30") (pin "1") (pinfunction "1_1") (pintype "passive"))
      (node (ref "C32") (pin "1") (pinfunction "1_1") (pintype "passive"))
      (node (ref "C34") (pin "1") (pinfunction "1_1") (pintype "passive"))
      (node (ref "C36") (pin "1") (pinfunction "1_1") (pintype "passive"))
      (node (ref "C39") (pin "1") (pinfunction "1_1") (pintype "passive"))
      (node (ref "C40") (pin "1") (pinfunction "1_1") (pintype "passive"))
      (node (ref "C42") (pin "1") (pinfunction "1_1") (pintype "passive"))
      (node (ref "C44") (pin "1") (pinfunction "1_1") (pintype "passive"))
      (node (ref "C45") (pin "1") (pinfunction "1_1") (pintype "passive"))
      (node (ref "C46") (pin "1") (pinfunction "1_1") (pintype "passive"))
      (node (ref "C48") (pin "1") (pinfunction "1_1") (pintype "passive"))
      (node (ref "C49") (pin "2") (pinfunction "2_2") (pintype "passive"))
      (node (ref "C50") (pin "2") (pinfunction "2_2") (pintype "passive"))
      (node (ref "C51") (pin "2") (pinfunction "2_2") (pintype "passive"))
      (node (ref "C52") (pin "1") (pinfunction "1_1") (pintype "passive"))
      (node (ref "C53") (pin "1") (pinfunction "1_1") (pintype "passive"))
      (node (ref "C55") (pin "1") (pinfunction "1_1") (pintype "passive"))
      (node (ref "C56") (pin "2") (pinfunction "2_2") (pintype "passive"))
      (node (ref "C58") (pin "1") (pinfunction "1_1") (pintype "passive"))
      (node (ref "C59") (pin "1") (pinfunction "1_1") (pintype "passive"))
      (node (ref "C60") (pin "2") (pinfunction "2_2") (pintype "passive"))
      (node (ref "C61") (pin "1") (pinfunction "1_1") (pintype "passive"))
      (node (ref "C62") (pin "1") (pinfunction "1_1") (pintype "passive"))
      (node (ref "C63") (pin "1") (pinfunction "1_1") (pintype "passive"))
      (node (ref "C64") (pin "1") (pinfunction "1_1") (pintype "passive"))
      (node (ref "C66") (pin "1") (pinfunction "1_1") (pintype "passive"))
      (node (ref "C68") (pin "1") (pinfunction "1_1") (pintype "passive"))
      (node (ref "C69") (pin "1") (pinfunction "1_1") (pintype "passive"))
      (node (ref "D8") (pin "2") (pinfunction "A_2") (pintype "passive"))
      (node (ref "D9") (pin "1") (pinfunction "C_1") (pintype "passive"))
      (node (ref "IC13") (pin "3") (pinfunction "GND_3") (pintype "power_in"))
      (node (ref "IC13") (pin "6") (pinfunction "GND_6") (pintype "power_in"))
      (node (ref "IC13") (pin "7") (pinfunction "GND_7") (pintype "power_in"))
      (node (ref "IC14") (pin "1") (pinfunction "GND_1") (pintype "power_in"))
      (node (ref "IC15") (pin "4") (pinfunction "V-_4") (pintype "power_in"))
      (node (ref "IC16") (pin "3") (pinfunction "GND_3") (pintype "power_in"))
      (node (ref "IC16") (pin "6") (pinfunction "GND_6") (pintype "power_in"))
      (node (ref "IC16") (pin "7") (pinfunction "GND_7") (pintype "power_in"))
      (node (ref "IC26") (pin "1") (pinfunction "PGND_1") (pintype "power_in"))
      (node (ref "IC26") (pin "11") (pinfunction "EP_11") (pintype "power_in"))
      (node (ref "IC26") (pin "6") (pinfunction "AGND_6") (pintype "power_in"))
      (node (ref "IC3") (pin "3") (pinfunction "-Vin_3") (pintype "power_in"))
      (node (ref "IC3") (pin "5") (pinfunction "COM_5") (pintype "power_in"))
      (node (ref "IC4") (pin "2") (pinfunction "GND_2") (pintype "power_in"))
      (node (ref "IC7") (pin "2") (pinfunction "GND_2") (pintype "power_in"))
      (node (ref "IC8") (pin "1") (pinfunction "PGND_1") (pintype "power_in"))
      (node (ref "IC8") (pin "11") (pinfunction "EP_11") (pintype "power_in"))
      (node (ref "IC8") (pin "6") (pinfunction "AGND_6") (pintype "power_in"))
      (node (ref "R143") (pin "1") (pinfunction "1_1") (pintype "passive"))
      (node (ref "R21") (pin "1") (pinfunction "1_1") (pintype "passive"))
      (node (ref "R27") (pin "1") (pinfunction "1_1") (pintype "passive"))
      (node (ref "R28") (pin "1") (pinfunction "1_1") (pintype "passive"))
      (node (ref "R29") (pin "1") (pinfunction "1_1") (pintype "passive"))
      (node (ref "R38") (pin "1") (pinfunction "1_1") (pintype "passive"))
      (node (ref "R48") (pin "1") (pinfunction "1_1") (pintype "passive"))
      (node (ref "R54") (pin "1") (pinfunction "1_1") (pintype "passive"))
      (node (ref "R8") (pin "1") (pinfunction "1_1") (pintype "passive"))
    )
    (net (code "4") (name "N12V0A") (class "Default")
      (node (ref "C46") (pin "2") (pinfunction "2_2") (pintype "passive"))
      (node (ref "C52") (pin "2") (pinfunction "2_2") (pintype "passive"))
      (node (ref "D9") (pin "2") (pinfunction "A_2") (pintype "passive"))
      (node (ref "IC14") (pin "5") (pinfunction "OUT_5") (pintype "power_in"))
      (node (ref "R32") (pin "2") (pinfunction "2_2") (pintype "passive"))
      (node (ref "TP9") (pin "1") (pinfunction "1_1") (pintype "bidirectional"))
    )
    (net (code "5") (name "N13V0") (class "Default")
      (node (ref "C19") (pin "2") (pinfunction "2_2") (pintype "passive"))
      (node (ref "C44") (pin "2") (pinfunction "2_2") (pintype "passive"))
      (node (ref "IC14") (pin "2") (pinfunction "IN_2") (pintype "input"))
      (node (ref "L13") (pin "2") (pinfunction "2_2") (pintype "passive"))
    )
    (net (code "6") (name "N13V0S") (class "Default")
      (node (ref "C40") (pin "2") (pinfunction "2_2") (pintype "passive"))
      (node (ref "IC3") (pin "4") (pinfunction "-Vout_4") (pintype "power_in"))
      (node (ref "L12") (pin "1") (pinfunction "1_1") (pintype "passive"))
      (node (ref "R19") (pin "1") (pinfunction "1_1") (pintype "passive"))
    )
    (net (code "7") (name "Net-(C18-Pad2)") (class "Default")
      (node (ref "C18") (pin "2") (pinfunction "2_2") (pintype "passive"))
      (node (ref "C42") (pin "2") (pinfunction "2_2") (pintype "passive"))
      (node (ref "L12") (pin "2") (pinfunction "2_2") (pintype "passive"))
      (node (ref "L13") (pin "1") (pinfunction "1_1") (pintype "passive"))
    )
    (net (code "8") (name "Net-(C27-Pad2)") (class "Default")
      (node (ref "C27") (pin "2") (pinfunction "2_2") (pintype "passive"))
      (node (ref "C28") (pin "1") (pinfunction "1_1") (pintype "passive"))
      (node (ref "L10") (pin "2") (pinfunction "2_2") (pintype "passive"))
      (node (ref "L11") (pin "1") (pinfunction "1_1") (pintype "passive"))
    )
    (net (code "9") (name "Net-(D2-A)") (class "Default")
      (node (ref "C68") (pin "2") (pinfunction "2_2") (pintype "passive"))
      (node (ref "D2") (pin "2") (pinfunction "A_2") (pintype "passive"))
      (node (ref "IC15") (pin "3") (pinfunction "IN+_3") (pintype "input"))
      (node (ref "R22") (pin "2") (pinfunction "2_2") (pintype "passive"))
      (node (ref "R48") (pin "2") (pinfunction "2_2") (pintype "passive"))
    )
    (net (code "10") (name "Net-(D4-A)") (class "Default")
      (node (ref "C69") (pin "2") (pinfunction "2_2") (pintype "passive"))
      (node (ref "D4") (pin "2") (pinfunction "A_2") (pintype "passive"))
      (node (ref "IC26") (pin "3") (pinfunction "EN_3") (pintype "input"))
      (node (ref "IC8") (pin "7") (pinfunction "PG_7") (pintype "output"))
      (node (ref "R56") (pin "1") (pinfunction "1_1") (pintype "passive"))
    )
    (net (code "11") (name "Net-(D5-A)") (class "Default")
      (node (ref "C66") (pin "2") (pinfunction "2_2") (pintype "passive"))
      (node (ref "D5") (pin "2") (pinfunction "A_2") (pintype "passive"))
      (node (ref "IC15") (pin "6") (pinfunction "IN-_6") (pintype "input"))
      (node (ref "R52") (pin "1") (pinfunction "1_1") (pintype "passive"))
    )
    (net (code "12") (name "Net-(D6-A)") (class "Default")
      (node (ref "D6") (pin "2") (pinfunction "A_2") (pintype "passive"))
      (node (ref "IC13") (pin "5") (pinfunction "~{SHDN}_5") (pintype "input"))
      (node (ref "IC14") (pin "3") (pinfunction "~{SHDN}_3") (pintype "input"))
      (node (ref "IC15") (pin "1") (pinfunction "OUT_1") (pintype "output"))
      (node (ref "R18") (pin "1") (pinfunction "1_1") (pintype "passive"))
      (node (ref "R52") (pin "2") (pinfunction "2_2") (pintype "passive"))
    )
    (net (code "13") (name "Net-(IC3-RC)") (class "Default")
      (node (ref "IC3") (pin "2") (pinfunction "RC_2") (pintype "input"))
      (node (ref "R8") (pin "2") (pinfunction "2_2") (pintype "passive"))
    )
    (net (code "14") (name "Net-(IC3-TRM)") (class "Default")
      (node (ref "IC3") (pin "6") (pinfunction "TRM_6") (pintype "power_in"))
      (node (ref "R19") (pin "2") (pinfunction "2_2") (pintype "passive"))
      (node (ref "R7") (pin "1") (pinfunction "1_1") (pintype "passive"))
    )
    (net (code "15") (name "Net-(IC4-ADJ)") (class "Default")
      (node (ref "IC4") (pin "4") (pinfunction "ADJ_4") (pintype "input"))
      (node (ref "R26") (pin "1") (pinfunction "1_1") (pintype "passive"))
      (node (ref "R27") (pin "2") (pinfunction "2_2") (pintype "passive"))
    )
    (net (code "16") (name "Net-(IC4-BYP)") (class "Default")
      (node (ref "C116") (pin "1") (pinfunction "1_1") (pintype "passive"))
      (node (ref "IC4") (pin "3") (pinfunction "BYP_3") (pintype "input"))
    )
    (net (code "17") (name "Net-(IC7-ADJ)") (class "Default")
      (node (ref "IC7") (pin "4") (pinfunction "ADJ_4") (pintype "input"))
      (node (ref "R53") (pin "1") (pinfunction "1_1") (pintype "passive"))
      (node (ref "R54") (pin "2") (pinfunction "2_2") (pintype "passive"))
    )
    (net (code "18") (name "Net-(IC7-BYP)") (class "Default")
      (node (ref "C47") (pin "1") (pinfunction "1_1") (pintype "passive"))
      (node (ref "IC7") (pin "3") (pinfunction "BYP_3") (pintype "input"))
    )
    (net (code "19") (name "Net-(IC8-FB)") (class "Default")
      (node (ref "IC8") (pin "5") (pinfunction "FB_5") (pintype "input"))
      (node (ref "R24") (pin "1") (pinfunction "1_1") (pintype "passive"))
      (node (ref "R28") (pin "2") (pinfunction "2_2") (pintype "passive"))
    )
    (net (code "20") (name "Net-(IC8-SW)") (class "Default")
      (node (ref "IC8") (pin "9") (pinfunction "SW_9") (pintype "output"))
      (node (ref "L3") (pin "1") (pinfunction "1_1") (pintype "passive"))
    )
    (net (code "21") (name "Net-(IC13-ADJ)") (class "Default")
      (node (ref "IC13") (pin "2") (pinfunction "ADJ_2") (pintype "input"))
      (node (ref "R142") (pin "1") (pinfunction "1_1") (pintype "passive"))
      (node (ref "R143") (pin "2") (pinfunction "2_2") (pintype "passive"))
    )
    (net (code "22") (name "Net-(IC13-BYP)") (class "Default")
      (node (ref "C65") (pin "1") (pinfunction "1_1") (pintype "passive"))
      (node (ref "IC13") (pin "4") (pinfunction "BYP_4") (pintype "passive"))
    )
    (net (code "23") (name "Net-(IC14-ADJ)") (class "Default")
      (node (ref "IC14") (pin "4") (pinfunction "ADJ_4") (pintype "input"))
      (node (ref "R32") (pin "1") (pinfunction "1_1") (pintype "passive"))
      (node (ref "R38") (pin "2") (pinfunction "2_2") (pintype "passive"))
    )
    (net (code "24") (name "Net-(IC15A-IN-)") (class "Default")
      (node (ref "IC15") (pin "2") (pinfunction "IN-_2") (pintype "input"))
      (node (ref "R23") (pin "1") (pinfunction "1_1") (pintype "passive"))
    )
    (net (code "25") (name "Net-(IC16-ADJ)") (class "Default")
      (node (ref "IC16") (pin "2") (pinfunction "ADJ_2") (pintype "input"))
      (node (ref "R25") (pin "1") (pinfunction "1_1") (pintype "passive"))
      (node (ref "R29") (pin "2") (pinfunction "2_2") (pintype "passive"))
    )
    (net (code "26") (name "Net-(IC16-BYP)") (class "Default")
      (node (ref "C114") (pin "1") (pinfunction "1_1") (pintype "passive"))
      (node (ref "IC16") (pin "4") (pinfunction "BYP_4") (pintype "passive"))
    )
    (net (code "27") (name "Net-(IC26-FB)") (class "Default")
      (node (ref "IC26") (pin "5") (pinfunction "FB_5") (pintype "input"))
      (node (ref "R20") (pin "1") (pinfunction "1_1") (pintype "passive"))
      (node (ref "R21") (pin "2") (pinfunction "2_2") (pintype "passive"))
    )
    (net (code "28") (name "Net-(IC26-SW)") (class "Default")
      (node (ref "IC26") (pin "9") (pinfunction "SW_9") (pintype "output"))
      (node (ref "L5") (pin "1") (pinfunction "1_1") (pintype "passive"))
    )
    (net (code "29") (name "Net-(IC26-VIN)") (class "Default")
      (node (ref "C122") (pin "2") (pinfunction "2_2") (pintype "passive"))
      (node (ref "C123") (pin "2") (pinfunction "2_2") (pintype "passive"))
      (node (ref "C32") (pin "2") (pinfunction "2_2") (pintype "passive"))
      (node (ref "C34") (pin "2") (pinfunction "2_2") (pintype "passive"))
      (node (ref "C36") (pin "2") (pinfunction "2_2") (pintype "passive"))
      (node (ref "C39") (pin "2") (pinfunction "2_2") (pintype "passive"))
      (node (ref "C49") (pin "1") (pinfunction "1_1") (pintype "passive"))
      (node (ref "C63") (pin "2") (pinfunction "2_2") (pintype "passive"))
      (node (ref "C64") (pin "2") (pinfunction "2_2") (pintype "passive"))
      (node (ref "IC26") (pin "2") (pinfunction "VIN_2") (pintype "input"))
      (node (ref "IC3") (pin "1") (pinfunction "+Vin_1") (pintype "power_in"))
      (node (ref "IC8") (pin "2") (pinfunction "VIN_2") (pintype "input"))
      (node (ref "IC8") (pin "3") (pinfunction "EN_3") (pintype "input"))
      (node (ref "L6") (pin "2") (pinfunction "2_2") (pintype "passive"))
    )
    (net (code "30") (name "P2V5A") (class "Default")
      (node (ref "C47") (pin "2") (pinfunction "2_2") (pintype "passive"))
      (node (ref "C55") (pin "2") (pinfunction "2_2") (pintype "passive"))
      (node (ref "C56") (pin "1") (pinfunction "1_1") (pintype "passive"))
      (node (ref "IC7") (pin "5") (pinfunction "OUT_5") (pintype "power_in"))
      (node (ref "R53") (pin "2") (pinfunction "2_2") (pintype "passive"))
      (node (ref "TP10") (pin "1") (pinfunction "1_1") (pintype "bidirectional"))
    )
    (net (code "31") (name "P3V3") (class "Default")
      (node (ref "C120") (pin "2") (pinfunction "2_2") (pintype "passive"))
      (node (ref "C121") (pin "2") (pinfunction "2_2") (pintype "passive"))
      (node (ref "D5") (pin "1") (pinfunction "C_1") (pintype "passive"))
      (node (ref "IC15") (pin "5") (pinfunction "IN+_5") (pintype "input"))
      (node (ref "IC26") (pin "10") (pinfunction "VOS_10") (pintype "input"))
      (node (ref "IC26") (pin "8") (pinfunction "SLEEP_8") (pintype "input"))
      (node (ref "L1") (pin "1") (pinfunction "1_1") (pintype "passive"))
      (node (ref "L5") (pin "2") (pinfunction "2_2") (pintype "passive"))
      (node (ref "R20") (pin "2") (pinfunction "2_2") (pintype "passive"))
      (node (ref "R51") (pin "1") (pinfunction "1_1") (pintype "passive"))
    )
    (net (code "32") (name "P3V3A") (class "Default")
      (node (ref "C50") (pin "1") (pinfunction "1_1") (pintype "passive"))
      (node (ref "C53") (pin "2") (pinfunction "2_2") (pintype "passive"))
      (node (ref "D2") (pin "1") (pinfunction "C_1") (pintype "passive"))
      (node (ref "IC7") (pin "1") (pinfunction "IN_1") (pintype "input"))
      (node (ref "L1") (pin "2") (pinfunction "2_2") (pintype "passive"))
      (node (ref "R23") (pin "2") (pinfunction "2_2") (pintype "passive"))
      (node (ref "TP11") (pin "1") (pinfunction "1_1") (pintype "bidirectional"))
    )
    (net (code "33") (name "P5V0A") (class "Default")
      (node (ref "C114") (pin "2") (pinfunction "2_2") (pintype "passive"))
      (node (ref "C115") (pin "1") (pinfunction "1_1") (pintype "passive"))
      (node (ref "C62") (pin "2") (pinfunction "2_2") (pintype "passive"))
      (node (ref "IC16") (pin "1") (pinfunction "OUT_1") (pintype "power_in"))
      (node (ref "R25") (pin "2") (pinfunction "2_2") (pintype "passive"))
      (node (ref "TP13") (pin "1") (pinfunction "1_1") (pintype "bidirectional"))
    )
    (net (code "34") (name "P6V0") (class "Default")
      (node (ref "C58") (pin "2") (pinfunction "2_2") (pintype "passive"))
      (node (ref "C59") (pin "2") (pinfunction "2_2") (pintype "passive"))
      (node (ref "IC8") (pin "10") (pinfunction "VOS_10") (pintype "input"))
      (node (ref "IC8") (pin "8") (pinfunction "SLEEP_8") (pintype "input"))
      (node (ref "L3") (pin "2") (pinfunction "2_2") (pintype "passive"))
      (node (ref "L4") (pin "1") (pinfunction "1_1") (pintype "passive"))
      (node (ref "R24") (pin "2") (pinfunction "2_2") (pintype "passive"))
      (node (ref "R57") (pin "2") (pinfunction "2_2") (pintype "passive"))
    )
    (net (code "35") (name "P6V0A") (class "Default")
      (node (ref "C60") (pin "1") (pinfunction "1_1") (pintype "passive"))
      (node (ref "C61") (pin "2") (pinfunction "2_2") (pintype "passive"))
      (node (ref "D4") (pin "1") (pinfunction "C_1") (pintype "passive"))
      (node (ref "IC16") (pin "5") (pinfunction "~{SHDN}_5") (pintype "input"))
      (node (ref "IC16") (pin "8") (pinfunction "IN_8") (pintype "input"))
      (node (ref "L4") (pin "2") (pinfunction "2_2") (pintype "passive"))
      (node (ref "R18") (pin "2") (pinfunction "2_2") (pintype "passive"))
      (node (ref "R56") (pin "2") (pinfunction "2_2") (pintype "passive"))
      (node (ref "TP12") (pin "1") (pinfunction "1_1") (pintype "bidirectional"))
    )
    (net (code "36") (name "P12V0") (class "Default")
      (node (ref "C48") (pin "2") (pinfunction "2_2") (pintype "passive"))
      (node (ref "IC15") (pin "8") (pinfunction "V+_8") (pintype "power_in"))
      (node (ref "L6") (pin "1") (pinfunction "1_1") (pintype "passive"))
    )
    (net (code "37") (name "P12V0A") (class "Default")
      (node (ref "C30") (pin "2") (pinfunction "2_2") (pintype "passive"))
      (node (ref "C51") (pin "1") (pinfunction "1_1") (pintype "passive"))
      (node (ref "C65") (pin "2") (pinfunction "2_2") (pintype "passive"))
      (node (ref "D8") (pin "1") (pinfunction "C_1") (pintype "passive"))
      (node (ref "IC13") (pin "1") (pinfunction "OUT_1") (pintype "power_in"))
      (node (ref "R142") (pin "2") (pinfunction "2_2") (pintype "passive"))
      (node (ref "TP7") (pin "1") (pinfunction "1_1") (pintype "bidirectional"))
    )
    (net (code "38") (name "P13V0") (class "Default")
      (node (ref "C112") (pin "2") (pinfunction "2_2") (pintype "passive"))
      (node (ref "C117") (pin "2") (pinfunction "2_2") (pintype "passive"))
      (node (ref "C29") (pin "2") (pinfunction "2_2") (pintype "passive"))
      (node (ref "IC13") (pin "8") (pinfunction "IN_8") (pintype "input"))
      (node (ref "IC4") (pin "1") (pinfunction "IN_1") (pintype "input"))
      (node (ref "L11") (pin "2") (pinfunction "2_2") (pintype "passive"))
    )
    (net (code "39") (name "P13V0S") (class "Default")
      (node (ref "C26") (pin "2") (pinfunction "2_2") (pintype "passive"))
      (node (ref "IC3") (pin "7") (pinfunction "+Vout_7") (pintype "power_in"))
      (node (ref "L10") (pin "1") (pinfunction "1_1") (pintype "passive"))
      (node (ref "R7") (pin "2") (pinfunction "2_2") (pintype "passive"))
    )
    (net (code "40") (name "REF_P5V0") (class "Default")
      (node (ref "R22") (pin "1") (pinfunction "1_1") (pintype "passive"))
    )
    (net (code "41") (name "REF_VCC") (class "Default")
      (node (ref "C116") (pin "2") (pinfunction "2_2") (pintype "passive"))
      (node (ref "C118") (pin "1") (pinfunction "1_1") (pintype "passive"))
      (node (ref "C45") (pin "2") (pinfunction "2_2") (pintype "passive"))
      (node (ref "IC4") (pin "5") (pinfunction "OUT_5") (pintype "power_in"))
      (node (ref "R26") (pin "2") (pinfunction "2_2") (pintype "passive"))
      (node (ref "TP8") (pin "1") (pinfunction "1_1") (pintype "bidirectional"))
    )
    (net (code "42") (name "unconnected-(IC8-NC-Pad4)") (class "Default")
      (node (ref "IC8") (pin "4") (pinfunction "NC_4") (pintype "passive"))
    )
    (net (code "43") (name "unconnected-(IC26-NC-Pad4)") (class "Default")
      (node (ref "IC26") (pin "4") (pinfunction "NC_4") (pintype "passive"))
    )
  )
)
